# ipp_8ch.net
KiCad netlist of a schematic drawn in EAGLE
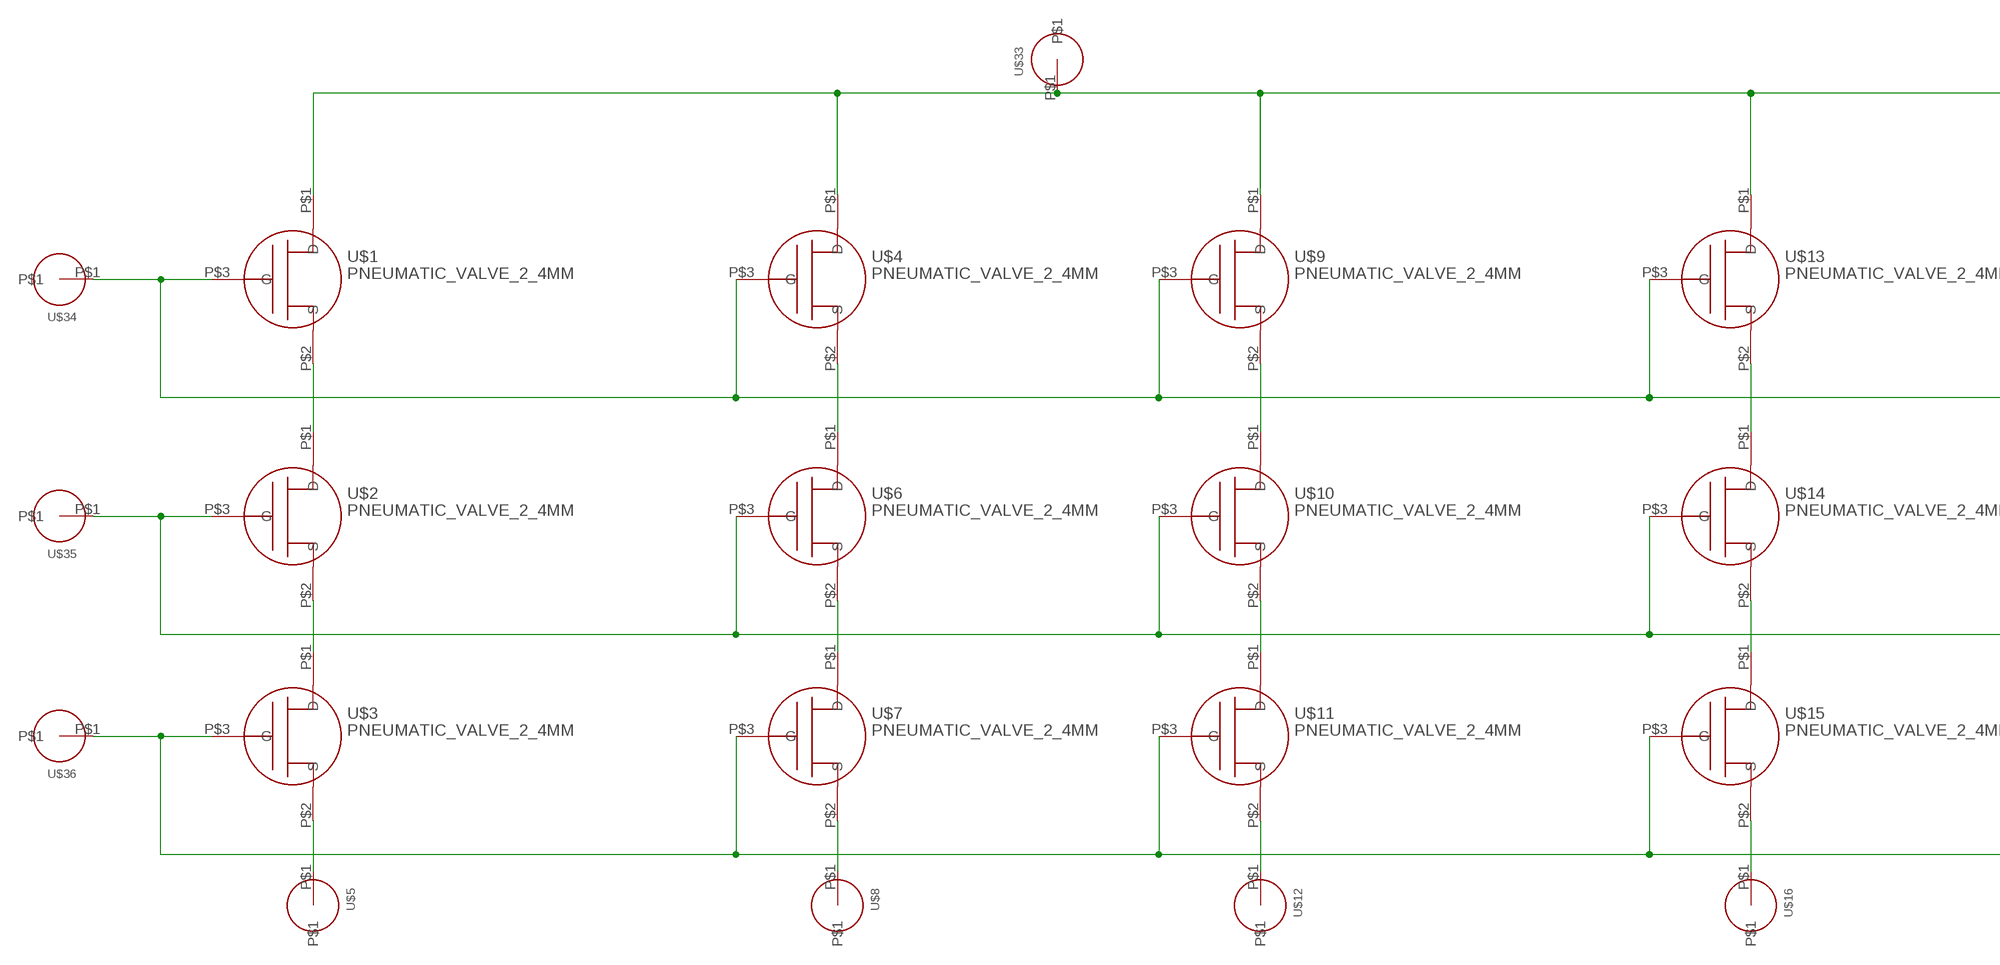
[diagram p0: schematic, sheet 1, part 1 of 2]
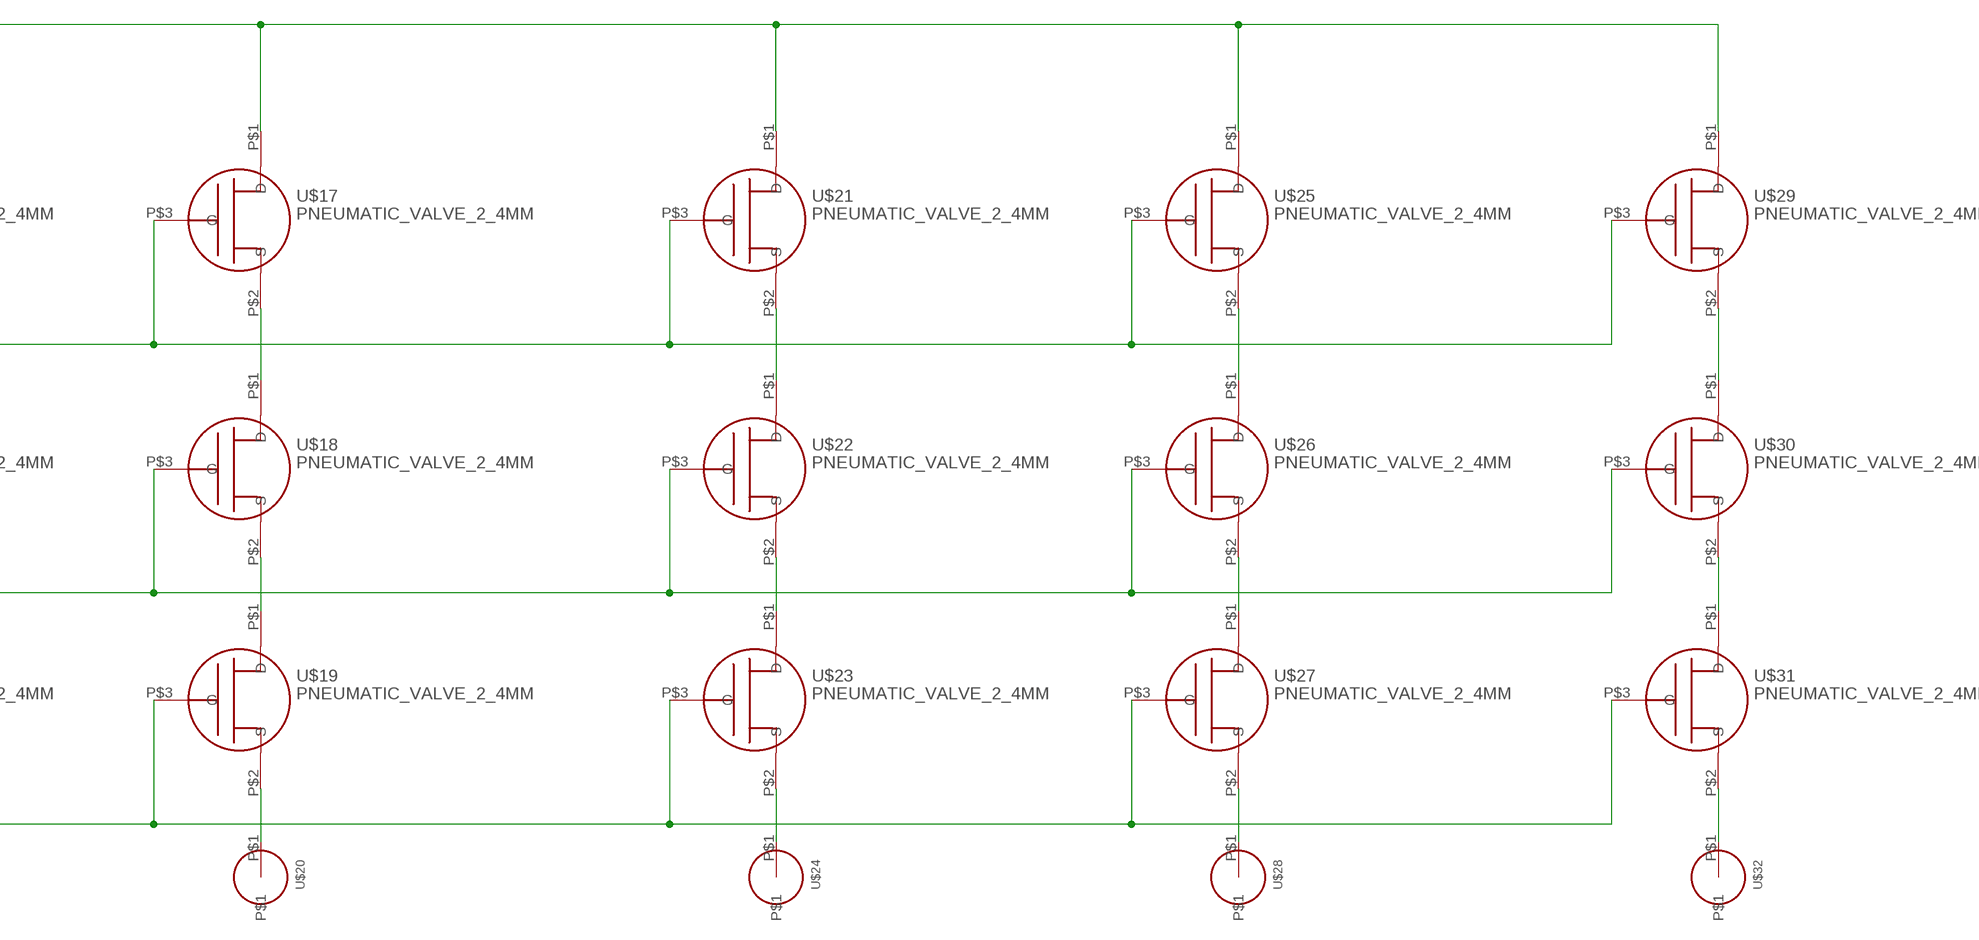
[diagram p1: schematic, sheet 1, part 2 of 2]

(export (version "E")
  (design (tool "Eeschema 10.0.6"))
  (components
    (comp (ref "U$1")
      (value "PNEUMATIC_VALVE_2_4MM")
      (footprint "eagle-import:2_4MM_PNEUMATIC_VALVE_C5_F4")
      (libsource (lib "eagle-import") (part "PNEUMATIC_VALVE_2_4MM"))
    )
    (comp (ref "U$2")
      (value "PNEUMATIC_VALVE_2_4MM")
      (footprint "eagle-import:2_4MM_PNEUMATIC_VALVE_C5_F4")
      (libsource (lib "eagle-import") (part "PNEUMATIC_VALVE_2_4MM"))
    )
    (comp (ref "U$3")
      (value "PNEUMATIC_VALVE_2_4MM")
      (footprint "eagle-import:2_4MM_PNEUMATIC_VALVE_C5_F4")
      (libsource (lib "eagle-import") (part "PNEUMATIC_VALVE_2_4MM"))
    )
    (comp (ref "U$4")
      (value "PNEUMATIC_VALVE_2_4MM")
      (footprint "eagle-import:2_4MM_PNEUMATIC_VALVE_C5_F4")
      (libsource (lib "eagle-import") (part "PNEUMATIC_VALVE_2_4MM"))
    )
    (comp (ref "U$5")
      (value "10-32_BARBED_CONNECTOR")
      (footprint "eagle-import:10-32_BARBED_CONNECTOR")
      (libsource (lib "eagle-import") (part "10-32_BARBED_CONNECTOR"))
    )
    (comp (ref "U$6")
      (value "PNEUMATIC_VALVE_2_4MM")
      (footprint "eagle-import:2_4MM_PNEUMATIC_VALVE_C5_F4")
      (libsource (lib "eagle-import") (part "PNEUMATIC_VALVE_2_4MM"))
    )
    (comp (ref "U$7")
      (value "PNEUMATIC_VALVE_2_4MM")
      (footprint "eagle-import:2_4MM_PNEUMATIC_VALVE_C5_F4")
      (libsource (lib "eagle-import") (part "PNEUMATIC_VALVE_2_4MM"))
    )
    (comp (ref "U$8")
      (value "10-32_BARBED_CONNECTOR")
      (footprint "eagle-import:10-32_BARBED_CONNECTOR")
      (libsource (lib "eagle-import") (part "10-32_BARBED_CONNECTOR"))
    )
    (comp (ref "U$9")
      (value "PNEUMATIC_VALVE_2_4MM")
      (footprint "eagle-import:2_4MM_PNEUMATIC_VALVE_C5_F4")
      (libsource (lib "eagle-import") (part "PNEUMATIC_VALVE_2_4MM"))
    )
    (comp (ref "U$10")
      (value "PNEUMATIC_VALVE_2_4MM")
      (footprint "eagle-import:2_4MM_PNEUMATIC_VALVE_C5_F4")
      (libsource (lib "eagle-import") (part "PNEUMATIC_VALVE_2_4MM"))
    )
    (comp (ref "U$11")
      (value "PNEUMATIC_VALVE_2_4MM")
      (footprint "eagle-import:2_4MM_PNEUMATIC_VALVE_C5_F4")
      (libsource (lib "eagle-import") (part "PNEUMATIC_VALVE_2_4MM"))
    )
    (comp (ref "U$12")
      (value "10-32_BARBED_CONNECTOR")
      (footprint "eagle-import:10-32_BARBED_CONNECTOR")
      (libsource (lib "eagle-import") (part "10-32_BARBED_CONNECTOR"))
    )
    (comp (ref "U$13")
      (value "PNEUMATIC_VALVE_2_4MM")
      (footprint "eagle-import:2_4MM_PNEUMATIC_VALVE_C5_F4")
      (libsource (lib "eagle-import") (part "PNEUMATIC_VALVE_2_4MM"))
    )
    (comp (ref "U$14")
      (value "PNEUMATIC_VALVE_2_4MM")
      (footprint "eagle-import:2_4MM_PNEUMATIC_VALVE_C5_F4")
      (libsource (lib "eagle-import") (part "PNEUMATIC_VALVE_2_4MM"))
    )
    (comp (ref "U$15")
      (value "PNEUMATIC_VALVE_2_4MM")
      (footprint "eagle-import:2_4MM_PNEUMATIC_VALVE_C5_F4")
      (libsource (lib "eagle-import") (part "PNEUMATIC_VALVE_2_4MM"))
    )
    (comp (ref "U$16")
      (value "10-32_BARBED_CONNECTOR")
      (footprint "eagle-import:10-32_BARBED_CONNECTOR")
      (libsource (lib "eagle-import") (part "10-32_BARBED_CONNECTOR"))
    )
    (comp (ref "U$17")
      (value "PNEUMATIC_VALVE_2_4MM")
      (footprint "eagle-import:2_4MM_PNEUMATIC_VALVE_C5_F4")
      (libsource (lib "eagle-import") (part "PNEUMATIC_VALVE_2_4MM"))
    )
    (comp (ref "U$18")
      (value "PNEUMATIC_VALVE_2_4MM")
      (footprint "eagle-import:2_4MM_PNEUMATIC_VALVE_C5_F4")
      (libsource (lib "eagle-import") (part "PNEUMATIC_VALVE_2_4MM"))
    )
    (comp (ref "U$19")
      (value "PNEUMATIC_VALVE_2_4MM")
      (footprint "eagle-import:2_4MM_PNEUMATIC_VALVE_C5_F4")
      (libsource (lib "eagle-import") (part "PNEUMATIC_VALVE_2_4MM"))
    )
    (comp (ref "U$20")
      (value "10-32_BARBED_CONNECTOR")
      (footprint "eagle-import:10-32_BARBED_CONNECTOR")
      (libsource (lib "eagle-import") (part "10-32_BARBED_CONNECTOR"))
    )
    (comp (ref "U$21")
      (value "PNEUMATIC_VALVE_2_4MM")
      (footprint "eagle-import:2_4MM_PNEUMATIC_VALVE_C5_F4")
      (libsource (lib "eagle-import") (part "PNEUMATIC_VALVE_2_4MM"))
    )
    (comp (ref "U$22")
      (value "PNEUMATIC_VALVE_2_4MM")
      (footprint "eagle-import:2_4MM_PNEUMATIC_VALVE_C5_F4")
      (libsource (lib "eagle-import") (part "PNEUMATIC_VALVE_2_4MM"))
    )
    (comp (ref "U$23")
      (value "PNEUMATIC_VALVE_2_4MM")
      (footprint "eagle-import:2_4MM_PNEUMATIC_VALVE_C5_F4")
      (libsource (lib "eagle-import") (part "PNEUMATIC_VALVE_2_4MM"))
    )
    (comp (ref "U$24")
      (value "10-32_BARBED_CONNECTOR")
      (footprint "eagle-import:10-32_BARBED_CONNECTOR")
      (libsource (lib "eagle-import") (part "10-32_BARBED_CONNECTOR"))
    )
    (comp (ref "U$25")
      (value "PNEUMATIC_VALVE_2_4MM")
      (footprint "eagle-import:2_4MM_PNEUMATIC_VALVE_C5_F4")
      (libsource (lib "eagle-import") (part "PNEUMATIC_VALVE_2_4MM"))
    )
    (comp (ref "U$26")
      (value "PNEUMATIC_VALVE_2_4MM")
      (footprint "eagle-import:2_4MM_PNEUMATIC_VALVE_C5_F4")
      (libsource (lib "eagle-import") (part "PNEUMATIC_VALVE_2_4MM"))
    )
    (comp (ref "U$27")
      (value "PNEUMATIC_VALVE_2_4MM")
      (footprint "eagle-import:2_4MM_PNEUMATIC_VALVE_C5_F4")
      (libsource (lib "eagle-import") (part "PNEUMATIC_VALVE_2_4MM"))
    )
    (comp (ref "U$28")
      (value "10-32_BARBED_CONNECTOR")
      (footprint "eagle-import:10-32_BARBED_CONNECTOR")
      (libsource (lib "eagle-import") (part "10-32_BARBED_CONNECTOR"))
    )
    (comp (ref "U$29")
      (value "PNEUMATIC_VALVE_2_4MM")
      (footprint "eagle-import:2_4MM_PNEUMATIC_VALVE_C5_F4")
      (libsource (lib "eagle-import") (part "PNEUMATIC_VALVE_2_4MM"))
    )
    (comp (ref "U$30")
      (value "PNEUMATIC_VALVE_2_4MM")
      (footprint "eagle-import:2_4MM_PNEUMATIC_VALVE_C5_F4")
      (libsource (lib "eagle-import") (part "PNEUMATIC_VALVE_2_4MM"))
    )
    (comp (ref "U$31")
      (value "PNEUMATIC_VALVE_2_4MM")
      (footprint "eagle-import:2_4MM_PNEUMATIC_VALVE_C5_F4")
      (libsource (lib "eagle-import") (part "PNEUMATIC_VALVE_2_4MM"))
    )
    (comp (ref "U$32")
      (value "10-32_BARBED_CONNECTOR")
      (footprint "eagle-import:10-32_BARBED_CONNECTOR")
      (libsource (lib "eagle-import") (part "10-32_BARBED_CONNECTOR"))
    )
    (comp (ref "U$33")
      (value "10-32_BARBED_CONNECTOR")
      (footprint "eagle-import:10-32_BARBED_CONNECTOR")
      (libsource (lib "eagle-import") (part "10-32_BARBED_CONNECTOR"))
    )
    (comp (ref "U$34")
      (value "10-32_BARBED_CONNECTOR")
      (footprint "eagle-import:10-32_BARBED_CONNECTOR")
      (libsource (lib "eagle-import") (part "10-32_BARBED_CONNECTOR"))
    )
    (comp (ref "U$35")
      (value "10-32_BARBED_CONNECTOR")
      (footprint "eagle-import:10-32_BARBED_CONNECTOR")
      (libsource (lib "eagle-import") (part "10-32_BARBED_CONNECTOR"))
    )
    (comp (ref "U$36")
      (value "10-32_BARBED_CONNECTOR")
      (footprint "eagle-import:10-32_BARBED_CONNECTOR")
      (libsource (lib "eagle-import") (part "10-32_BARBED_CONNECTOR"))
    )
  )
  (nets
    (net (code "1") (name "Net-(U$1-D)") (class "Default")
      (node (ref "U$1") (pin "P$1") (pinfunction "D_P$1") (pintype "bidirectional"))
      (node (ref "U$13") (pin "P$1") (pinfunction "D_P$1") (pintype "bidirectional"))
      (node (ref "U$17") (pin "P$1") (pinfunction "D_P$1") (pintype "bidirectional"))
      (node (ref "U$21") (pin "P$1") (pinfunction "D_P$1") (pintype "bidirectional"))
      (node (ref "U$25") (pin "P$1") (pinfunction "D_P$1") (pintype "bidirectional"))
      (node (ref "U$29") (pin "P$1") (pinfunction "D_P$1") (pintype "bidirectional"))
      (node (ref "U$33") (pin "P$1") (pinfunction "P$1_P$1") (pintype "bidirectional"))
      (node (ref "U$4") (pin "P$1") (pinfunction "D_P$1") (pintype "bidirectional"))
      (node (ref "U$9") (pin "P$1") (pinfunction "D_P$1") (pintype "bidirectional"))
    )
    (net (code "2") (name "Net-(U$1-G)") (class "Default")
      (node (ref "U$1") (pin "P$3") (pinfunction "G_P$3") (pintype "bidirectional"))
      (node (ref "U$13") (pin "P$3") (pinfunction "G_P$3") (pintype "bidirectional"))
      (node (ref "U$17") (pin "P$3") (pinfunction "G_P$3") (pintype "bidirectional"))
      (node (ref "U$21") (pin "P$3") (pinfunction "G_P$3") (pintype "bidirectional"))
      (node (ref "U$25") (pin "P$3") (pinfunction "G_P$3") (pintype "bidirectional"))
      (node (ref "U$29") (pin "P$3") (pinfunction "G_P$3") (pintype "bidirectional"))
      (node (ref "U$34") (pin "P$1") (pinfunction "P$1_P$1") (pintype "bidirectional"))
      (node (ref "U$4") (pin "P$3") (pinfunction "G_P$3") (pintype "bidirectional"))
      (node (ref "U$9") (pin "P$3") (pinfunction "G_P$3") (pintype "bidirectional"))
    )
    (net (code "3") (name "Net-(U$1-S)") (class "Default")
      (node (ref "U$1") (pin "P$2") (pinfunction "S_P$2") (pintype "bidirectional"))
      (node (ref "U$2") (pin "P$1") (pinfunction "D_P$1") (pintype "bidirectional"))
    )
    (net (code "4") (name "Net-(U$2-S)") (class "Default")
      (node (ref "U$2") (pin "P$2") (pinfunction "S_P$2") (pintype "bidirectional"))
      (node (ref "U$3") (pin "P$1") (pinfunction "D_P$1") (pintype "bidirectional"))
    )
    (net (code "5") (name "Net-(U$3-S)") (class "Default")
      (node (ref "U$3") (pin "P$2") (pinfunction "S_P$2") (pintype "bidirectional"))
      (node (ref "U$5") (pin "P$1") (pinfunction "P$1_P$1") (pintype "bidirectional"))
    )
    (net (code "6") (name "Net-(U$4-S)") (class "Default")
      (node (ref "U$4") (pin "P$2") (pinfunction "S_P$2") (pintype "bidirectional"))
      (node (ref "U$6") (pin "P$1") (pinfunction "D_P$1") (pintype "bidirectional"))
    )
    (net (code "7") (name "Net-(U$6-S)") (class "Default")
      (node (ref "U$6") (pin "P$2") (pinfunction "S_P$2") (pintype "bidirectional"))
      (node (ref "U$7") (pin "P$1") (pinfunction "D_P$1") (pintype "bidirectional"))
    )
    (net (code "8") (name "Net-(U$7-S)") (class "Default")
      (node (ref "U$7") (pin "P$2") (pinfunction "S_P$2") (pintype "bidirectional"))
      (node (ref "U$8") (pin "P$1") (pinfunction "P$1_P$1") (pintype "bidirectional"))
    )
    (net (code "9") (name "Net-(U$10-D)") (class "Default")
      (node (ref "U$10") (pin "P$1") (pinfunction "D_P$1") (pintype "bidirectional"))
      (node (ref "U$9") (pin "P$2") (pinfunction "S_P$2") (pintype "bidirectional"))
    )
    (net (code "10") (name "Net-(U$10-G)") (class "Default")
      (node (ref "U$10") (pin "P$3") (pinfunction "G_P$3") (pintype "bidirectional"))
      (node (ref "U$14") (pin "P$3") (pinfunction "G_P$3") (pintype "bidirectional"))
      (node (ref "U$18") (pin "P$3") (pinfunction "G_P$3") (pintype "bidirectional"))
      (node (ref "U$2") (pin "P$3") (pinfunction "G_P$3") (pintype "bidirectional"))
      (node (ref "U$22") (pin "P$3") (pinfunction "G_P$3") (pintype "bidirectional"))
      (node (ref "U$26") (pin "P$3") (pinfunction "G_P$3") (pintype "bidirectional"))
      (node (ref "U$30") (pin "P$3") (pinfunction "G_P$3") (pintype "bidirectional"))
      (node (ref "U$35") (pin "P$1") (pinfunction "P$1_P$1") (pintype "bidirectional"))
      (node (ref "U$6") (pin "P$3") (pinfunction "G_P$3") (pintype "bidirectional"))
    )
    (net (code "11") (name "Net-(U$10-S)") (class "Default")
      (node (ref "U$10") (pin "P$2") (pinfunction "S_P$2") (pintype "bidirectional"))
      (node (ref "U$11") (pin "P$1") (pinfunction "D_P$1") (pintype "bidirectional"))
    )
    (net (code "12") (name "Net-(U$11-G)") (class "Default")
      (node (ref "U$11") (pin "P$3") (pinfunction "G_P$3") (pintype "bidirectional"))
      (node (ref "U$15") (pin "P$3") (pinfunction "G_P$3") (pintype "bidirectional"))
      (node (ref "U$19") (pin "P$3") (pinfunction "G_P$3") (pintype "bidirectional"))
      (node (ref "U$23") (pin "P$3") (pinfunction "G_P$3") (pintype "bidirectional"))
      (node (ref "U$27") (pin "P$3") (pinfunction "G_P$3") (pintype "bidirectional"))
      (node (ref "U$3") (pin "P$3") (pinfunction "G_P$3") (pintype "bidirectional"))
      (node (ref "U$31") (pin "P$3") (pinfunction "G_P$3") (pintype "bidirectional"))
      (node (ref "U$36") (pin "P$1") (pinfunction "P$1_P$1") (pintype "bidirectional"))
      (node (ref "U$7") (pin "P$3") (pinfunction "G_P$3") (pintype "bidirectional"))
    )
    (net (code "13") (name "Net-(U$11-S)") (class "Default")
      (node (ref "U$11") (pin "P$2") (pinfunction "S_P$2") (pintype "bidirectional"))
      (node (ref "U$12") (pin "P$1") (pinfunction "P$1_P$1") (pintype "bidirectional"))
    )
    (net (code "14") (name "Net-(U$13-S)") (class "Default")
      (node (ref "U$13") (pin "P$2") (pinfunction "S_P$2") (pintype "bidirectional"))
      (node (ref "U$14") (pin "P$1") (pinfunction "D_P$1") (pintype "bidirectional"))
    )
    (net (code "15") (name "Net-(U$14-S)") (class "Default")
      (node (ref "U$14") (pin "P$2") (pinfunction "S_P$2") (pintype "bidirectional"))
      (node (ref "U$15") (pin "P$1") (pinfunction "D_P$1") (pintype "bidirectional"))
    )
    (net (code "16") (name "Net-(U$15-S)") (class "Default")
      (node (ref "U$15") (pin "P$2") (pinfunction "S_P$2") (pintype "bidirectional"))
      (node (ref "U$16") (pin "P$1") (pinfunction "P$1_P$1") (pintype "bidirectional"))
    )
    (net (code "17") (name "Net-(U$17-S)") (class "Default")
      (node (ref "U$17") (pin "P$2") (pinfunction "S_P$2") (pintype "bidirectional"))
      (node (ref "U$18") (pin "P$1") (pinfunction "D_P$1") (pintype "bidirectional"))
    )
    (net (code "18") (name "Net-(U$18-S)") (class "Default")
      (node (ref "U$18") (pin "P$2") (pinfunction "S_P$2") (pintype "bidirectional"))
      (node (ref "U$19") (pin "P$1") (pinfunction "D_P$1") (pintype "bidirectional"))
    )
    (net (code "19") (name "Net-(U$19-S)") (class "Default")
      (node (ref "U$19") (pin "P$2") (pinfunction "S_P$2") (pintype "bidirectional"))
      (node (ref "U$20") (pin "P$1") (pinfunction "P$1_P$1") (pintype "bidirectional"))
    )
    (net (code "20") (name "Net-(U$21-S)") (class "Default")
      (node (ref "U$21") (pin "P$2") (pinfunction "S_P$2") (pintype "bidirectional"))
      (node (ref "U$22") (pin "P$1") (pinfunction "D_P$1") (pintype "bidirectional"))
    )
    (net (code "21") (name "Net-(U$22-S)") (class "Default")
      (node (ref "U$22") (pin "P$2") (pinfunction "S_P$2") (pintype "bidirectional"))
      (node (ref "U$23") (pin "P$1") (pinfunction "D_P$1") (pintype "bidirectional"))
    )
    (net (code "22") (name "Net-(U$23-S)") (class "Default")
      (node (ref "U$23") (pin "P$2") (pinfunction "S_P$2") (pintype "bidirectional"))
      (node (ref "U$24") (pin "P$1") (pinfunction "P$1_P$1") (pintype "bidirectional"))
    )
    (net (code "23") (name "Net-(U$25-S)") (class "Default")
      (node (ref "U$25") (pin "P$2") (pinfunction "S_P$2") (pintype "bidirectional"))
      (node (ref "U$26") (pin "P$1") (pinfunction "D_P$1") (pintype "bidirectional"))
    )
    (net (code "24") (name "Net-(U$26-S)") (class "Default")
      (node (ref "U$26") (pin "P$2") (pinfunction "S_P$2") (pintype "bidirectional"))
      (node (ref "U$27") (pin "P$1") (pinfunction "D_P$1") (pintype "bidirectional"))
    )
    (net (code "25") (name "Net-(U$27-S)") (class "Default")
      (node (ref "U$27") (pin "P$2") (pinfunction "S_P$2") (pintype "bidirectional"))
      (node (ref "U$28") (pin "P$1") (pinfunction "P$1_P$1") (pintype "bidirectional"))
    )
    (net (code "26") (name "Net-(U$29-S)") (class "Default")
      (node (ref "U$29") (pin "P$2") (pinfunction "S_P$2") (pintype "bidirectional"))
      (node (ref "U$30") (pin "P$1") (pinfunction "D_P$1") (pintype "bidirectional"))
    )
    (net (code "27") (name "Net-(U$30-S)") (class "Default")
      (node (ref "U$30") (pin "P$2") (pinfunction "S_P$2") (pintype "bidirectional"))
      (node (ref "U$31") (pin "P$1") (pinfunction "D_P$1") (pintype "bidirectional"))
    )
    (net (code "28") (name "Net-(U$31-S)") (class "Default")
      (node (ref "U$31") (pin "P$2") (pinfunction "S_P$2") (pintype "bidirectional"))
      (node (ref "U$32") (pin "P$1") (pinfunction "P$1_P$1") (pintype "bidirectional"))
    )
  )
)
